# DCDC_Jetson.net
KiCad netlist of a schematic drawn in Altium Designer
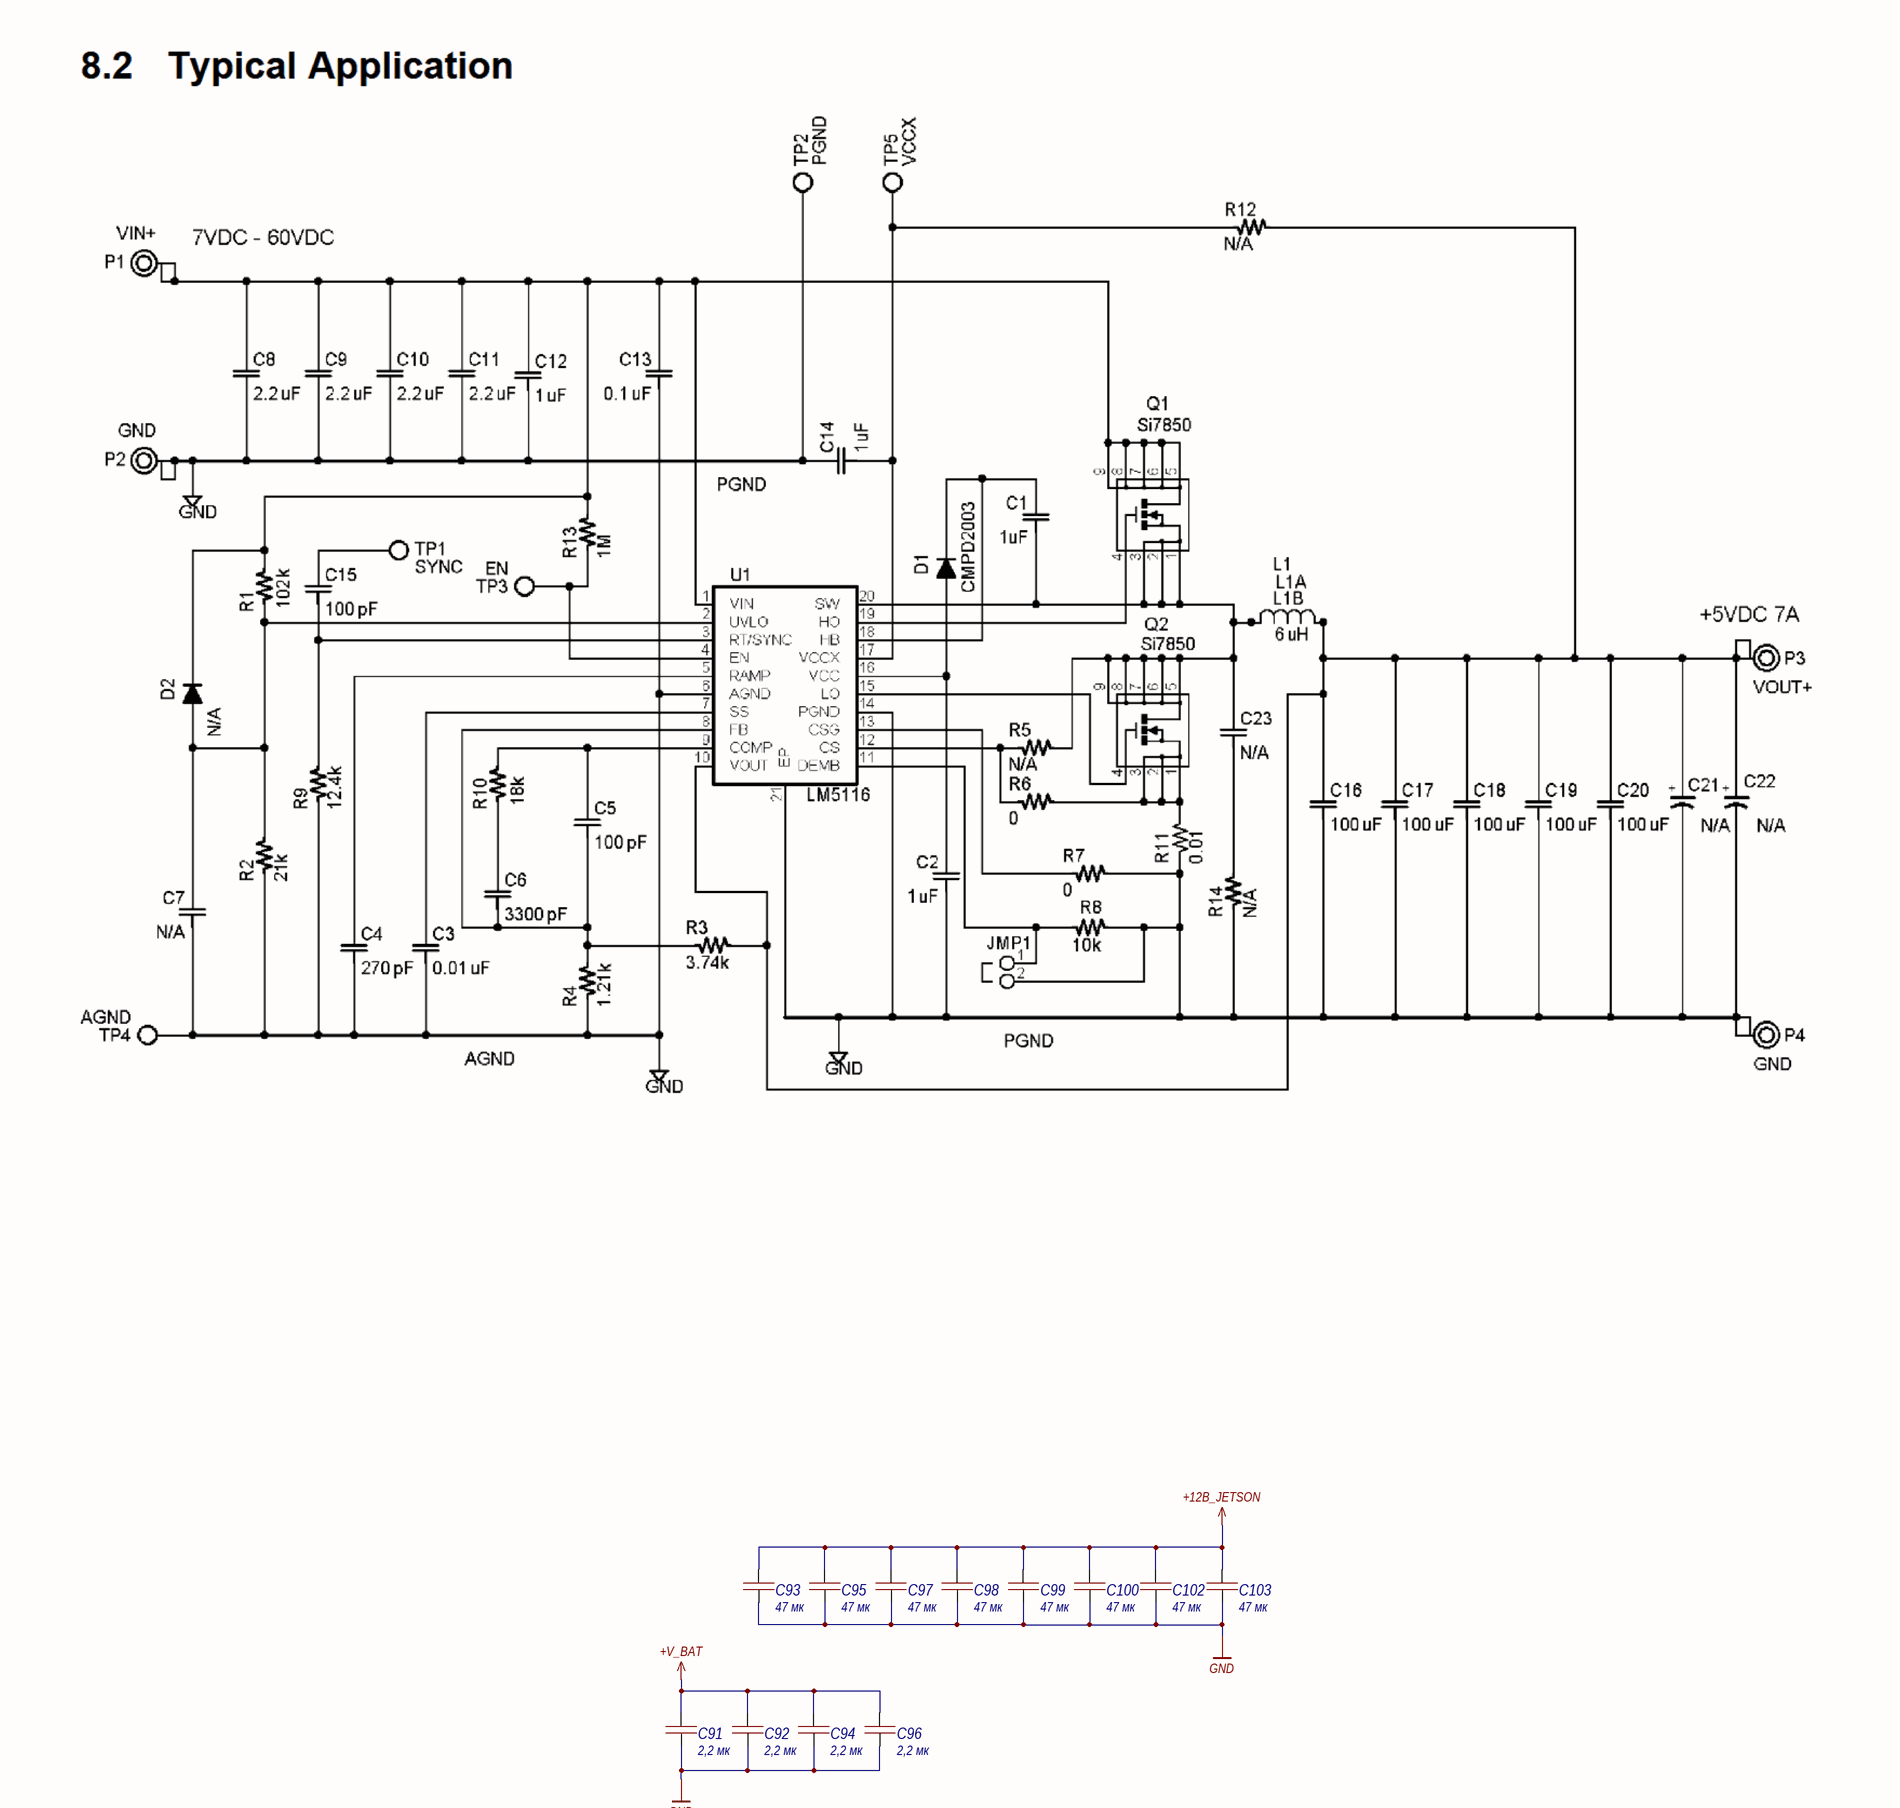
[diagram p0: DCDC_Jetson.SchDoc, top]
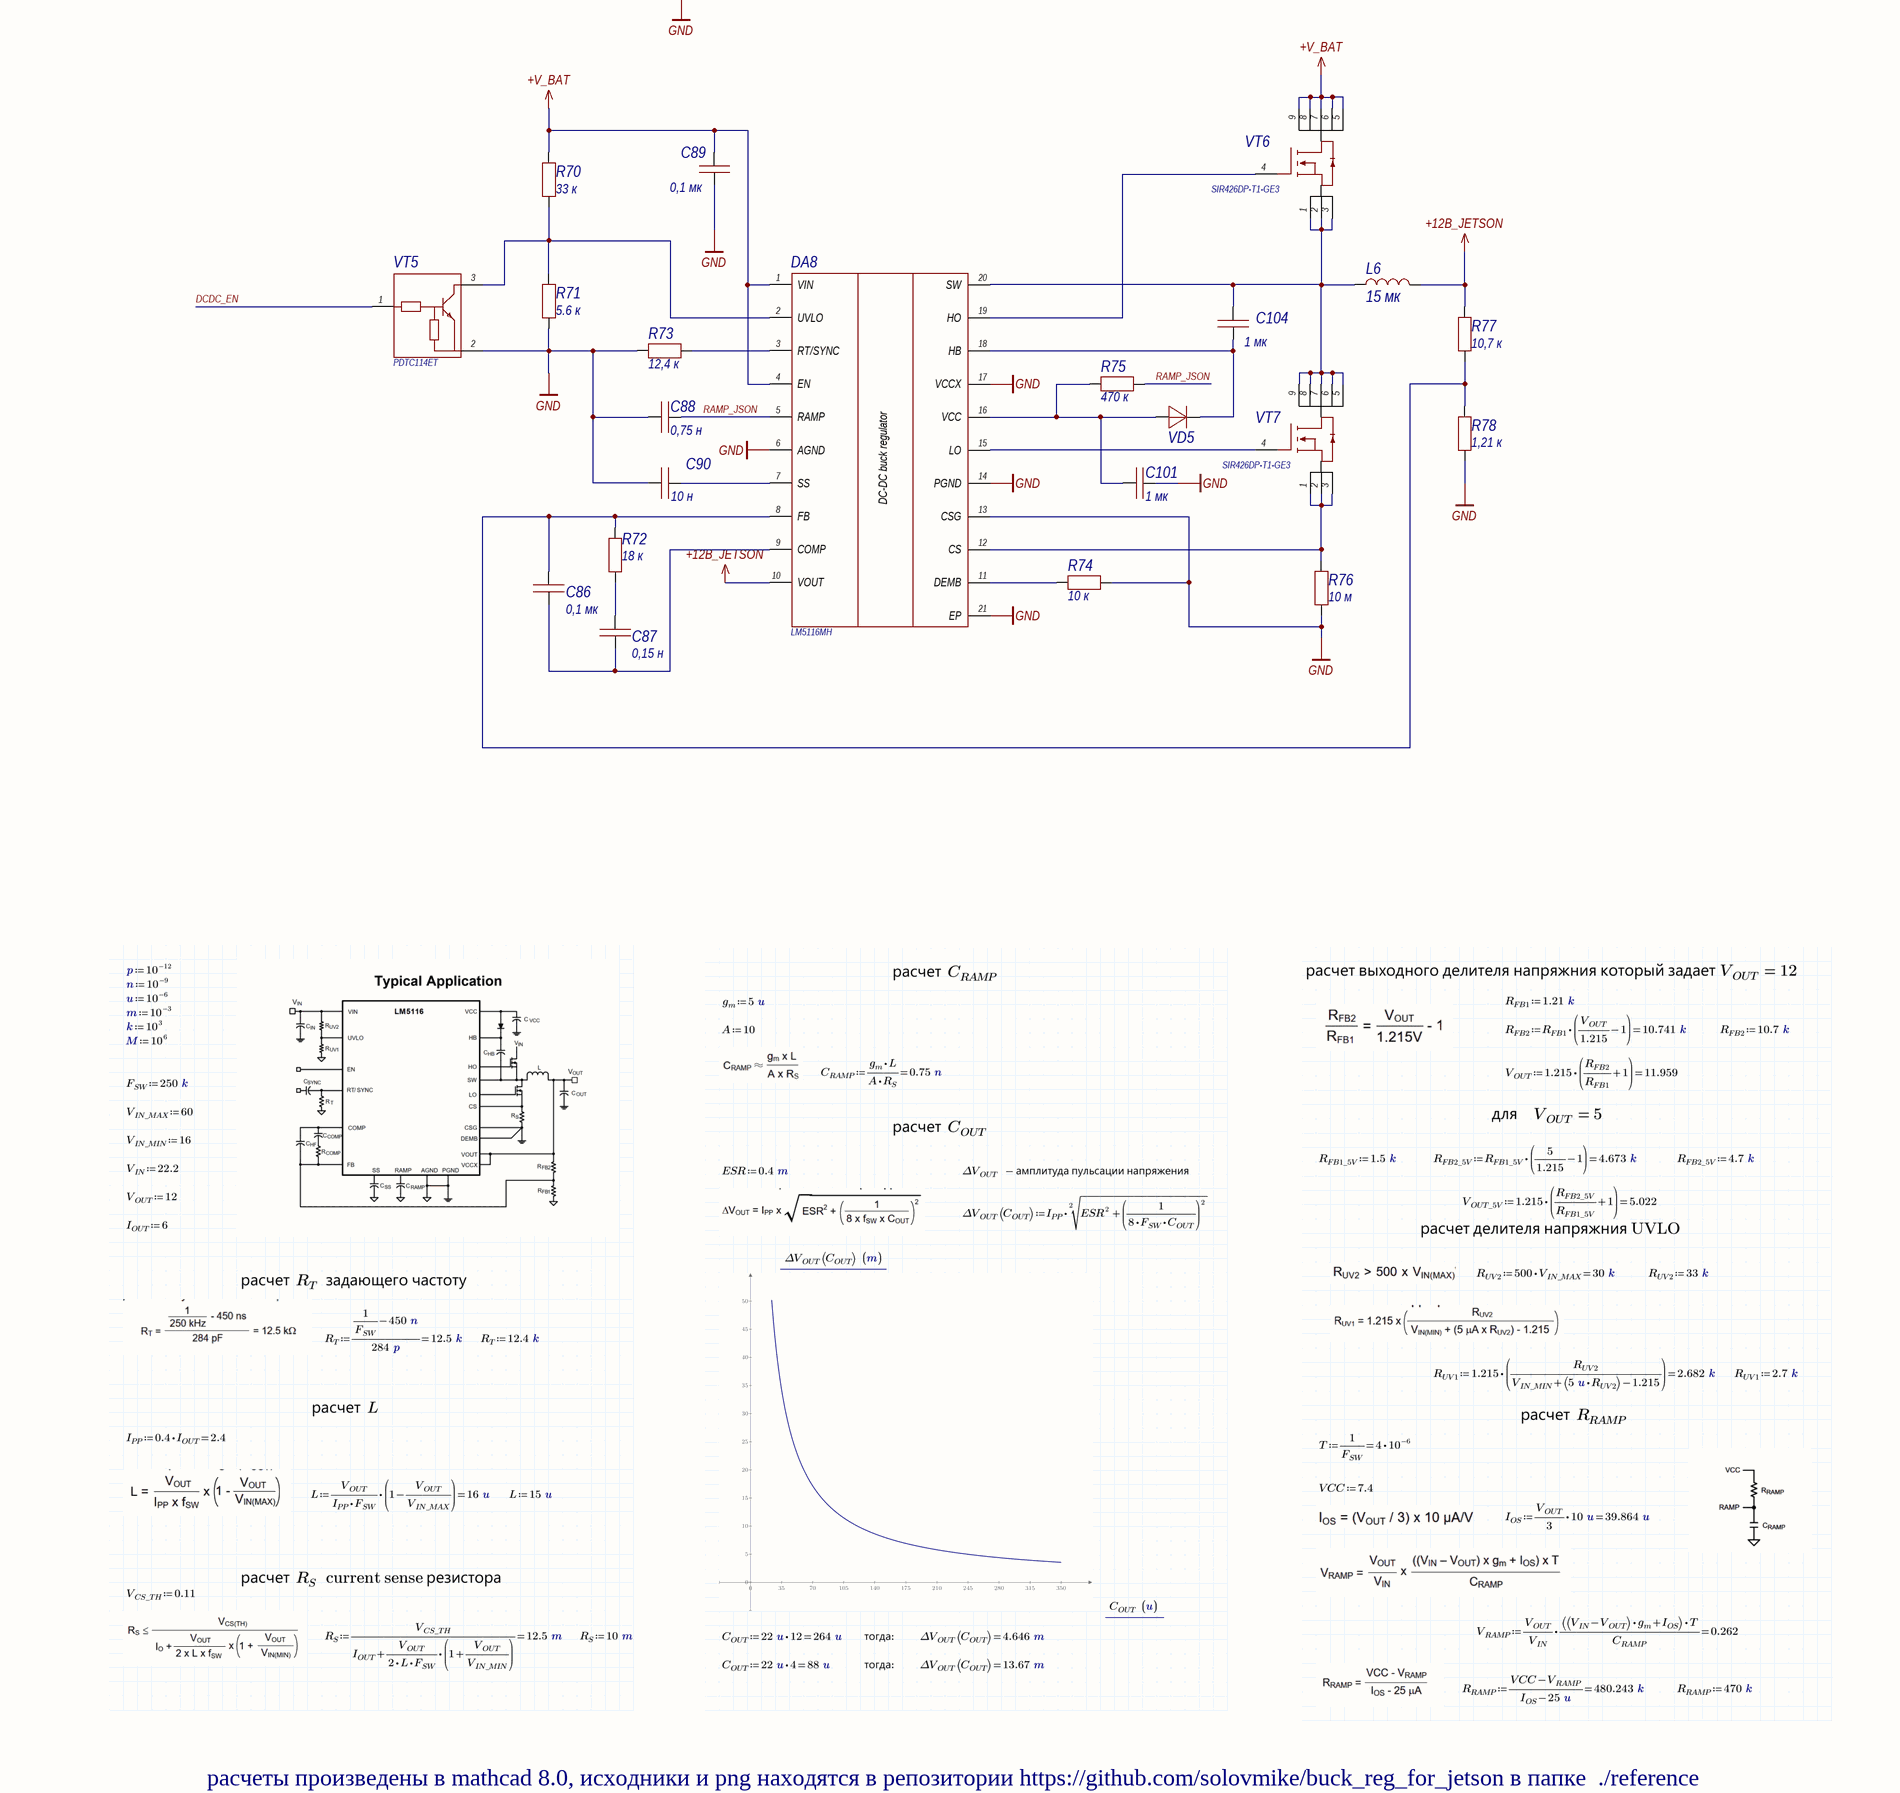
[diagram p1: DCDC_Jetson.SchDoc, bottom]

(export (version "E")
  (design (tool "Eeschema 10.0.6"))
  (components
    (comp (ref "C86")
      (value "0,1 мк")
      (footprint "0603C")
      (description "Конденсатор 0603C ёмкостью 0,1 мк 10%, 50 В, X7R")
      (fields (field (name "PART NUMBER") "Capacitor_0,1u_10_50V_X7R_0603C") (field (name "TOLERANCE") "10%"))
      (libsource (lib "Hydrolib") (part "Capacitor"))
    )
    (comp (ref "C87")
      (value "0,15 н")
      (footprint "0603C")
      (description "Конденсатор")
      (fields
        (field (name "PART NUMBER") "Capacitor_0,15n_10_50V_X7R_0603C")
        (field (name "TOLERANCE") "0,1")
      )
      (libsource (lib "Hydrolib") (part "Capacitor"))
    )
    (comp (ref "C88")
      (value "0,75 н")
      (footprint "0603C")
      (description "Конденсатор")
      (fields
        (field (name "PART NUMBER") "Capacitor_0,75n_10_50V_X7R_0603C")
        (field (name "TOLERANCE") "0,1")
      )
      (libsource (lib "Hydrolib") (part "Capacitor"))
    )
    (comp (ref "C89")
      (value "0,1 мк")
      (footprint "0603C")
      (description "Конденсатор")
      (fields (field (name "PART NUMBER") "Capacitor_0,1u_10_50V_X7R_0603C") (field (name "TOLERANCE") "0,1"))
      (libsource (lib "Hydrolib") (part "Capacitor"))
    )
    (comp (ref "C90")
      (value "10 н")
      (footprint "0603C")
      (description "Конденсатор")
      (fields (field (name "PART NUMBER") "Capacitor_10n_10_50V_X7R_0603C") (field (name "TOLERANCE") "0,1"))
      (libsource (lib "Hydrolib") (part "Capacitor"))
    )
    (comp (ref "C91")
      (value "2,2 мк")
      (footprint "1206C")
      (description "Конденсатор 1206C ёмкостью 2,2 мк 10%, 50 В, X7R")
      (fields (field (name "PART NUMBER") "Capacitor_2,2u_10_50V_X7R_1206C") (field (name "TOLERANCE") "10%"))
      (libsource (lib "Hydrolib") (part "Capacitor"))
    )
    (comp (ref "C92")
      (value "2,2 мк")
      (footprint "1206C")
      (description "Конденсатор 1206C ёмкостью 2,2 мк 10%, 50 В, X7R")
      (fields (field (name "PART NUMBER") "Capacitor_2,2u_10_50V_X7R_1206C") (field (name "TOLERANCE") "10%"))
      (libsource (lib "Hydrolib") (part "Capacitor"))
    )
    (comp (ref "C93")
      (value "47 мк")
      (footprint "1206C")
      (description "Конденсатор 1206C ёмкостью 47 мк 20%, 25 В, X5R")
      (fields
        (field (name "PART NUMBER") "GRM31CR61E476ME44L")
        (field (name "TOLERANCE") "20%")
        (field (name "АВТОР") "rreali")
      )
      (libsource (lib "Hydrolib") (part "Capacitor"))
    )
    (comp (ref "C94")
      (value "2,2 мк")
      (footprint "1206C")
      (description "Конденсатор 1206C ёмкостью 2,2 мк 10%, 50 В, X7R")
      (fields (field (name "PART NUMBER") "Capacitor_2,2u_10_50V_X7R_1206C") (field (name "TOLERANCE") "10%"))
      (libsource (lib "Hydrolib") (part "Capacitor"))
    )
    (comp (ref "C95")
      (value "47 мк")
      (footprint "1206C")
      (description "Конденсатор 1206C ёмкостью 47 мк 20%, 25 В, X5R")
      (fields
        (field (name "PART NUMBER") "GRM31CR61E476ME44L")
        (field (name "TOLERANCE") "20%")
        (field (name "АВТОР") "rreali")
      )
      (libsource (lib "Hydrolib") (part "Capacitor"))
    )
    (comp (ref "C96")
      (value "2,2 мк")
      (footprint "1206C")
      (description "Конденсатор 1206C ёмкостью 2,2 мк 10%, 50 В, X7R")
      (fields (field (name "PART NUMBER") "Capacitor_2,2u_10_50V_X7R_1206C") (field (name "TOLERANCE") "10%"))
      (libsource (lib "Hydrolib") (part "Capacitor"))
    )
    (comp (ref "C97")
      (value "47 мк")
      (footprint "1206C")
      (description "Конденсатор 1206C ёмкостью 47 мк 20%, 25 В, X5R")
      (fields
        (field (name "PART NUMBER") "GRM31CR61E476ME44L")
        (field (name "TOLERANCE") "20%")
        (field (name "АВТОР") "rreali")
      )
      (libsource (lib "Hydrolib") (part "Capacitor"))
    )
    (comp (ref "C98")
      (value "47 мк")
      (footprint "1206C")
      (description "Конденсатор 1206C ёмкостью 47 мк 20%, 25 В, X5R")
      (fields
        (field (name "PART NUMBER") "GRM31CR61E476ME44L")
        (field (name "TOLERANCE") "20%")
        (field (name "АВТОР") "rreali")
      )
      (libsource (lib "Hydrolib") (part "Capacitor"))
    )
    (comp (ref "C99")
      (value "47 мк")
      (footprint "1206C")
      (description "Конденсатор 1206C ёмкостью 47 мк 20%, 25 В, X5R")
      (fields
        (field (name "PART NUMBER") "GRM31CR61E476ME44L")
        (field (name "TOLERANCE") "20%")
        (field (name "АВТОР") "rreali")
      )
      (libsource (lib "Hydrolib") (part "Capacitor"))
    )
    (comp (ref "C100")
      (value "47 мк")
      (footprint "1206C")
      (description "Конденсатор 1206C ёмкостью 47 мк 20%, 25 В, X5R")
      (fields
        (field (name "PART NUMBER") "GRM31CR61E476ME44L")
        (field (name "TOLERANCE") "20%")
        (field (name "АВТОР") "rreali")
      )
      (libsource (lib "Hydrolib") (part "Capacitor"))
    )
    (comp (ref "C101")
      (value "1 мк")
      (footprint "0603C")
      (description "Конденсатор")
      (fields (field (name "PART NUMBER") "Capacitor_1u_10_50V_X7R_0603C") (field (name "TOLERANCE") "0,1"))
      (libsource (lib "Hydrolib") (part "Capacitor"))
    )
    (comp (ref "C102")
      (value "47 мк")
      (footprint "1206C")
      (description "Конденсатор 1206C ёмкостью 47 мк 20%, 25 В, X5R")
      (fields
        (field (name "PART NUMBER") "GRM31CR61E476ME44L")
        (field (name "TOLERANCE") "20%")
        (field (name "АВТОР") "rreali")
      )
      (libsource (lib "Hydrolib") (part "Capacitor"))
    )
    (comp (ref "C103")
      (value "47 мк")
      (footprint "1206C")
      (description "Конденсатор 1206C ёмкостью 47 мк 20%, 25 В, X5R")
      (fields
        (field (name "PART NUMBER") "GRM31CR61E476ME44L")
        (field (name "TOLERANCE") "20%")
        (field (name "АВТОР") "rreali")
      )
      (libsource (lib "Hydrolib") (part "Capacitor"))
    )
    (comp (ref "C104")
      (value "1 мк")
      (footprint "0603C")
      (description "Конденсатор")
      (fields (field (name "PART NUMBER") "Capacitor_1u_10_50V_X7R_0603C") (field (name "TOLERANCE") "0,1"))
      (libsource (lib "Hydrolib") (part "Capacitor"))
    )
    (comp (ref "DA8")
      (value "LM5116MH")
      (footprint "HTSSOP-20")
      (description "dc-dc понижающий adj 6-100v")
      (fields (field (name "MANUFACTURER_PART_NUMBER") "LM5116MH/NOPB"))
      (libsource (lib "Hydrolib") (part "LM5116MH"))
    )
    (comp (ref "L6")
      (value "15 мк")
      (footprint "IHLP-4040")
      (description "Катушка индуктивности SMD экранированная 15мкГн ±20% 6,25A 45мОм")
      (fields (field (name "PART NUMBER") "IHLP4040DZER150M11") (field (name "АВТОР") "rreali"))
      (libsource (lib "Hydrolib") (part "Inductance"))
    )
    (comp (ref "R70")
      (value "33 к")
      (footprint "0603R")
      (description "Резистор номиналом 33 кОм и точностью 1%")
      (fields (field (name "PART NUMBER") "Resistor_33k_1_0603") (field (name "TOLERANCE") "1%"))
      (libsource (lib "") (part "Resistor_1"))
    )
    (comp (ref "R71")
      (value "5.6 к")
      (footprint "0603R")
      (description "Резистор номиналом 2,7 кОм и точностью 1%")
      (fields (field (name "PART NUMBER") "Resistor_2.7k_1_0603") (field (name "TOLERANCE") "1%"))
      (libsource (lib "") (part "Resistor_1"))
    )
    (comp (ref "R72")
      (value "18 к")
      (footprint "0603R")
      (description "Резистор номиналом 18 кОм 1%")
      (fields (field (name "PART NUMBER") "Resistor_18k_1_0603") (field (name "TOLERANCE") "1%"))
      (libsource (lib "") (part "Resistor_1"))
    )
    (comp (ref "R73")
      (value "12,4 к")
      (footprint "0603R")
      (description "Резистор номиналом 12,4 кОм и точностью 1%")
      (fields (field (name "PART NUMBER") "Resistor_12.4k_1_0603") (field (name "TOLERANCE") "1%"))
      (libsource (lib "Hydrolib") (part "Resistor"))
    )
    (comp (ref "R74")
      (value "10 к")
      (footprint "0603R")
      (description "Резистор номиналом 10 кОм и точностью 1%")
      (fields (field (name "PART NUMBER") "Resistor_10k_1_0603") (field (name "TOLERANCE") "1%"))
      (libsource (lib "Hydrolib") (part "Resistor"))
    )
    (comp (ref "R75")
      (value "470 к")
      (footprint "0603R")
      (description "Резистор номиналом 470 кОм и точностью 1%")
      (fields (field (name "PART NUMBER") "Resistor_470k_1_0603") (field (name "TOLERANCE") "1%"))
      (libsource (lib "Hydrolib") (part "Resistor"))
    )
    (comp (ref "R76")
      (value "10 м")
      (footprint "1210R")
      (description "Резистор номиналом 10 мОм, точностью 1%, 0.5Вт")
      (fields (field (name "PART NUMBER") "RL1210FR-070R01L") (field (name "TOLERANCE") "1%"))
      (libsource (lib "") (part "Resistor_1"))
    )
    (comp (ref "R77")
      (value "10,7 к")
      (footprint "0603R")
      (description "Резистор номиналом 10,7 кОм 1%")
      (fields (field (name "PART NUMBER") "Resistor_10.7k_1_0603") (field (name "TOLERANCE") "1%"))
      (libsource (lib "") (part "Resistor_1"))
    )
    (comp (ref "R78")
      (value "1,21 к")
      (footprint "0603R")
      (description "Резистор номиналом 1,21 кОм 1%")
      (fields (field (name "PART NUMBER") "Resistor_1.21k_1_0603") (field (name "TOLERANCE") "1%"))
      (libsource (lib "") (part "Resistor_1"))
    )
    (comp (ref "VD5")
      (value "S1GFL")
      (footprint "SOD-123F")
      (description "Диод 400В 1A [SOD-123F]")
      (fields (field (name "АВТОР") "rreali"))
      (libsource (lib "Hydrolib") (part "Rectifier_diode"))
    )
    (comp (ref "VT5")
      (value "PDTC114ET")
      (footprint "SOT23-3")
      (description "цифровой npn 50в 100мА")
      (libsource (lib "Hydrolib") (part "PDTC114ET"))
    )
    (comp (ref "VT6")
      (value "SIR426DP-T1-GE3")
      (footprint "PowerPAK_SO-8")
      (description "Транзистор полевой MOSFET N-канальный 40В 41.7Вт")
      (libsource (lib "Hydrolib") (part "SIR426DP-T1-GE3"))
    )
    (comp (ref "VT7")
      (value "SIR426DP-T1-GE3")
      (footprint "PowerPAK_SO-8")
      (description "Транзистор полевой MOSFET N-канальный 40В 41.7Вт")
      (libsource (lib "Hydrolib") (part "SIR426DP-T1-GE3"))
    )
  )
  (nets
    (net (code "1") (name "+12В_JETSON") (class "Default")
      (node (ref "C100") (pin "2") (pinfunction "2_2") (pintype "passive"))
      (node (ref "C102") (pin "2") (pinfunction "2_2") (pintype "passive"))
      (node (ref "C103") (pin "2") (pinfunction "2_2") (pintype "passive"))
      (node (ref "C93") (pin "2") (pinfunction "2_2") (pintype "passive"))
      (node (ref "C95") (pin "2") (pinfunction "2_2") (pintype "passive"))
      (node (ref "C97") (pin "2") (pinfunction "2_2") (pintype "passive"))
      (node (ref "C98") (pin "2") (pinfunction "2_2") (pintype "passive"))
      (node (ref "C99") (pin "2") (pinfunction "2_2") (pintype "passive"))
      (node (ref "DA8") (pin "10") (pinfunction "VOUT_10") (pintype "passive"))
      (node (ref "L6") (pin "2") (pinfunction "2_2") (pintype "passive"))
      (node (ref "R77") (pin "2") (pinfunction "2_2") (pintype "passive"))
    )
    (net (code "2") (name "+V_BAT") (class "Default")
      (node (ref "C89") (pin "2") (pinfunction "2_2") (pintype "passive"))
      (node (ref "C91") (pin "2") (pinfunction "2_2") (pintype "passive"))
      (node (ref "C92") (pin "2") (pinfunction "2_2") (pintype "passive"))
      (node (ref "C94") (pin "2") (pinfunction "2_2") (pintype "passive"))
      (node (ref "C96") (pin "2") (pinfunction "2_2") (pintype "passive"))
      (node (ref "DA8") (pin "1") (pinfunction "VIN_1") (pintype "passive"))
      (node (ref "DA8") (pin "4") (pinfunction "EN_4") (pintype "passive"))
      (node (ref "R70") (pin "2") (pinfunction "2_2") (pintype "passive"))
      (node (ref "VT6") (pin "5") (pinfunction "5_5") (pintype "passive"))
      (node (ref "VT6") (pin "6") (pinfunction "6_6") (pintype "passive"))
      (node (ref "VT6") (pin "7") (pinfunction "7_7") (pintype "passive"))
      (node (ref "VT6") (pin "8") (pinfunction "8_8") (pintype "passive"))
      (node (ref "VT6") (pin "9") (pinfunction "9_9") (pintype "passive"))
    )
    (net (code "3") (name "/DCDC_EN") (class "Default")
      (node (ref "VT5") (pin "1") (pinfunction "B_1") (pintype "passive"))
    )
    (net (code "4") (name "/RAMP_JSON") (class "Default")
      (node (ref "C88") (pin "2") (pinfunction "2_2") (pintype "passive"))
      (node (ref "DA8") (pin "5") (pinfunction "RAMP_5") (pintype "passive"))
      (node (ref "R75") (pin "2") (pinfunction "2_2") (pintype "passive"))
    )
    (net (code "5") (name "GND") (class "Default")
      (node (ref "C100") (pin "1") (pinfunction "1_1") (pintype "passive"))
      (node (ref "C101") (pin "2") (pinfunction "2_2") (pintype "passive"))
      (node (ref "C102") (pin "1") (pinfunction "1_1") (pintype "passive"))
      (node (ref "C103") (pin "1") (pinfunction "1_1") (pintype "passive"))
      (node (ref "C88") (pin "1") (pinfunction "1_1") (pintype "passive"))
      (node (ref "C89") (pin "1") (pinfunction "1_1") (pintype "passive"))
      (node (ref "C90") (pin "1") (pinfunction "1_1") (pintype "passive"))
      (node (ref "C91") (pin "1") (pinfunction "1_1") (pintype "passive"))
      (node (ref "C92") (pin "1") (pinfunction "1_1") (pintype "passive"))
      (node (ref "C93") (pin "1") (pinfunction "1_1") (pintype "passive"))
      (node (ref "C94") (pin "1") (pinfunction "1_1") (pintype "passive"))
      (node (ref "C95") (pin "1") (pinfunction "1_1") (pintype "passive"))
      (node (ref "C96") (pin "1") (pinfunction "1_1") (pintype "passive"))
      (node (ref "C97") (pin "1") (pinfunction "1_1") (pintype "passive"))
      (node (ref "C98") (pin "1") (pinfunction "1_1") (pintype "passive"))
      (node (ref "C99") (pin "1") (pinfunction "1_1") (pintype "passive"))
      (node (ref "DA8") (pin "13") (pinfunction "CSG_13") (pintype "passive"))
      (node (ref "DA8") (pin "14") (pinfunction "PGND_14") (pintype "passive"))
      (node (ref "DA8") (pin "17") (pinfunction "VCCX_17") (pintype "passive"))
      (node (ref "DA8") (pin "21") (pinfunction "EP_21") (pintype "passive"))
      (node (ref "DA8") (pin "6") (pinfunction "AGND_6") (pintype "passive"))
      (node (ref "R71") (pin "1") (pinfunction "1_1") (pintype "passive"))
      (node (ref "R73") (pin "1") (pinfunction "1_1") (pintype "passive"))
      (node (ref "R74") (pin "2") (pinfunction "2_2") (pintype "passive"))
      (node (ref "R76") (pin "1") (pinfunction "1_1") (pintype "passive"))
      (node (ref "R78") (pin "1") (pinfunction "1_1") (pintype "passive"))
      (node (ref "VT5") (pin "2") (pinfunction "E_2") (pintype "passive"))
    )
    (net (code "6") (name "Net-(C87-Pad2)") (class "Default")
      (node (ref "C87") (pin "2") (pinfunction "2_2") (pintype "passive"))
      (node (ref "R72") (pin "1") (pinfunction "1_1") (pintype "passive"))
    )
    (net (code "7") (name "Net-(DA8-COMP)") (class "Default")
      (node (ref "C86") (pin "1") (pinfunction "1_1") (pintype "passive"))
      (node (ref "C87") (pin "1") (pinfunction "1_1") (pintype "passive"))
      (node (ref "DA8") (pin "9") (pinfunction "COMP_9") (pintype "passive"))
    )
    (net (code "8") (name "Net-(DA8-CS)") (class "Default")
      (node (ref "DA8") (pin "12") (pinfunction "CS_12") (pintype "passive"))
      (node (ref "R76") (pin "2") (pinfunction "2_2") (pintype "passive"))
      (node (ref "VT7") (pin "1") (pinfunction "1_1") (pintype "passive"))
      (node (ref "VT7") (pin "2") (pinfunction "2_2") (pintype "passive"))
      (node (ref "VT7") (pin "3") (pinfunction "3_3") (pintype "passive"))
    )
    (net (code "9") (name "Net-(DA8-DEMB)") (class "Default")
      (node (ref "DA8") (pin "11") (pinfunction "DEMB_11") (pintype "passive"))
      (node (ref "R74") (pin "1") (pinfunction "1_1") (pintype "passive"))
    )
    (net (code "10") (name "Net-(DA8-FB)") (class "Default")
      (node (ref "C86") (pin "2") (pinfunction "2_2") (pintype "passive"))
      (node (ref "DA8") (pin "8") (pinfunction "FB_8") (pintype "passive"))
      (node (ref "R72") (pin "2") (pinfunction "2_2") (pintype "passive"))
      (node (ref "R77") (pin "1") (pinfunction "1_1") (pintype "passive"))
      (node (ref "R78") (pin "2") (pinfunction "2_2") (pintype "passive"))
    )
    (net (code "11") (name "Net-(DA8-HB)") (class "Default")
      (node (ref "C104") (pin "1") (pinfunction "1_1") (pintype "passive"))
      (node (ref "DA8") (pin "18") (pinfunction "HB_18") (pintype "passive"))
      (node (ref "VD5") (pin "2") (pinfunction "2_2") (pintype "passive"))
    )
    (net (code "12") (name "Net-(DA8-HO)") (class "Default")
      (node (ref "DA8") (pin "19") (pinfunction "HO_19") (pintype "passive"))
      (node (ref "VT6") (pin "4") (pinfunction "4_4") (pintype "passive"))
    )
    (net (code "13") (name "Net-(DA8-LO)") (class "Default")
      (node (ref "DA8") (pin "15") (pinfunction "LO_15") (pintype "passive"))
      (node (ref "VT7") (pin "4") (pinfunction "4_4") (pintype "passive"))
    )
    (net (code "14") (name "Net-(DA8-RT{slash}SYNC)") (class "Default")
      (node (ref "DA8") (pin "3") (pinfunction "RT/SYNC_3") (pintype "passive"))
      (node (ref "R73") (pin "2") (pinfunction "2_2") (pintype "passive"))
    )
    (net (code "15") (name "Net-(DA8-SS)") (class "Default")
      (node (ref "C90") (pin "2") (pinfunction "2_2") (pintype "passive"))
      (node (ref "DA8") (pin "7") (pinfunction "SS_7") (pintype "passive"))
    )
    (net (code "16") (name "Net-(DA8-SW)") (class "Default")
      (node (ref "C104") (pin "2") (pinfunction "2_2") (pintype "passive"))
      (node (ref "DA8") (pin "20") (pinfunction "SW_20") (pintype "passive"))
      (node (ref "L6") (pin "1") (pinfunction "1_1") (pintype "passive"))
      (node (ref "VT6") (pin "1") (pinfunction "1_1") (pintype "passive"))
      (node (ref "VT6") (pin "2") (pinfunction "2_2") (pintype "passive"))
      (node (ref "VT6") (pin "3") (pinfunction "3_3") (pintype "passive"))
      (node (ref "VT7") (pin "5") (pinfunction "5_5") (pintype "passive"))
      (node (ref "VT7") (pin "6") (pinfunction "6_6") (pintype "passive"))
      (node (ref "VT7") (pin "7") (pinfunction "7_7") (pintype "passive"))
      (node (ref "VT7") (pin "8") (pinfunction "8_8") (pintype "passive"))
      (node (ref "VT7") (pin "9") (pinfunction "9_9") (pintype "passive"))
    )
    (net (code "17") (name "Net-(DA8-UVLO)") (class "Default")
      (node (ref "DA8") (pin "2") (pinfunction "UVLO_2") (pintype "passive"))
      (node (ref "R70") (pin "1") (pinfunction "1_1") (pintype "passive"))
      (node (ref "R71") (pin "2") (pinfunction "2_2") (pintype "passive"))
      (node (ref "VT5") (pin "3") (pinfunction "C_3") (pintype "passive"))
    )
    (net (code "18") (name "Net-(DA8-VCC)") (class "Default")
      (node (ref "C101") (pin "1") (pinfunction "1_1") (pintype "passive"))
      (node (ref "DA8") (pin "16") (pinfunction "VCC_16") (pintype "passive"))
      (node (ref "R75") (pin "1") (pinfunction "1_1") (pintype "passive"))
      (node (ref "VD5") (pin "1") (pinfunction "1_1") (pintype "passive"))
    )
  )
)
